# DSI_LCD.net
KiCad netlist of a schematic drawn in Altium Designer
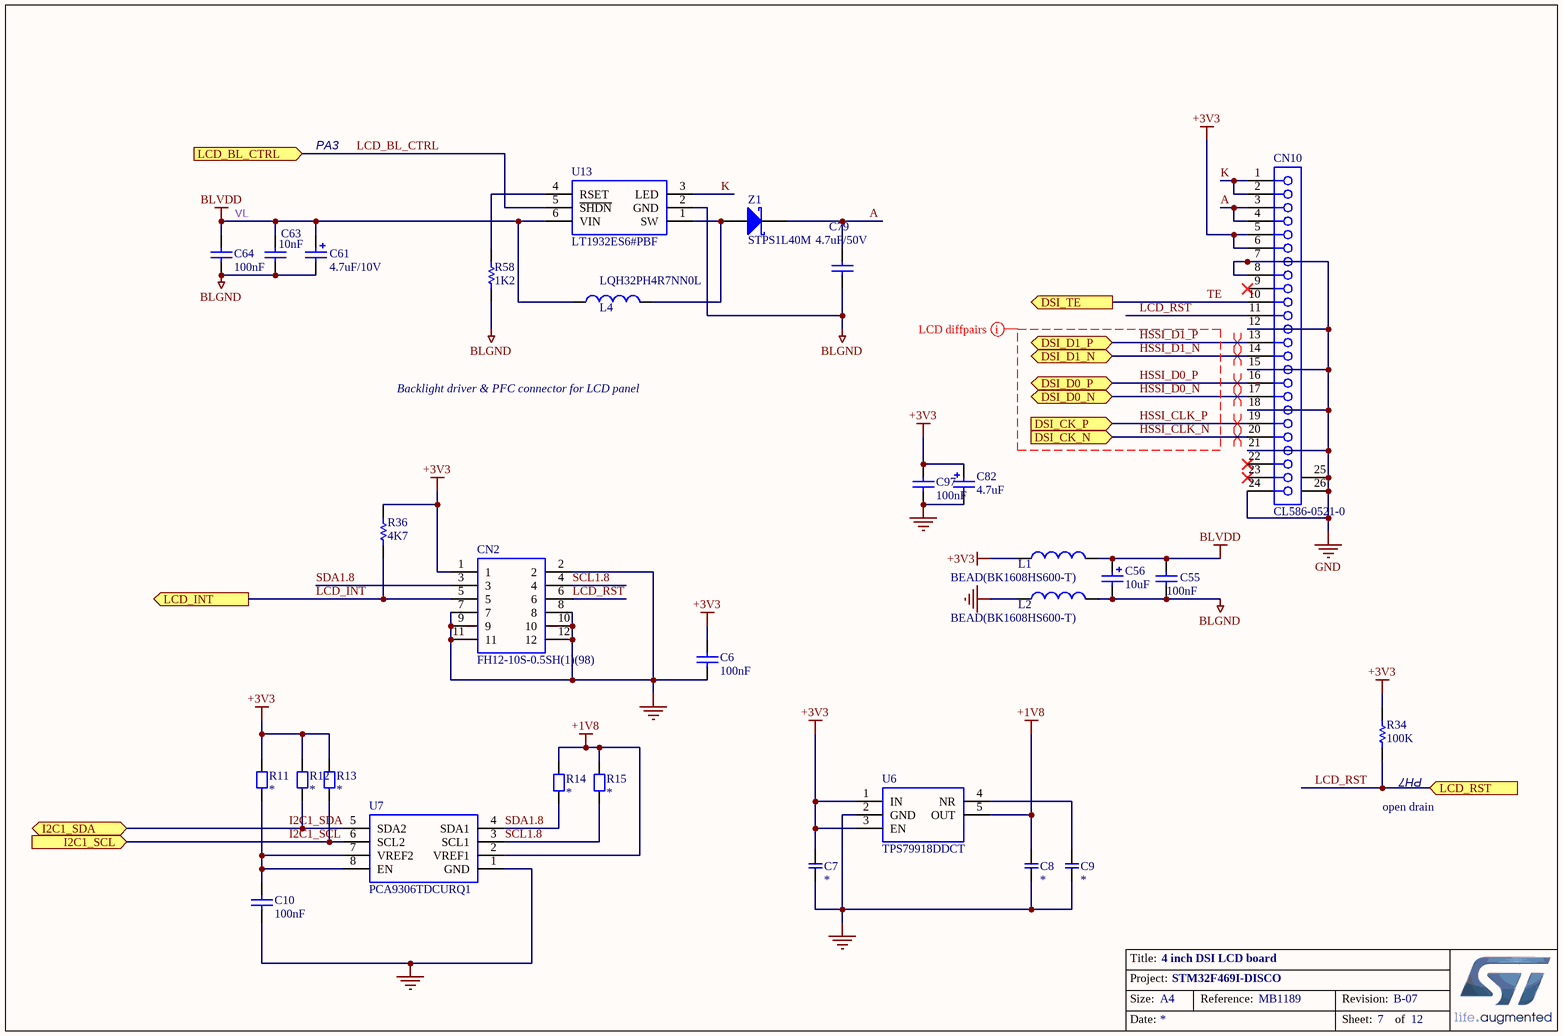
[diagram p0: DSI_LCD.SchDoc]

(export (version "E")
  (design (tool "Eeschema 10.0.6"))
  (components
    (comp (ref "C6")
      (value "100nF")
      (footprint "CAP - 0402")
      (description "Capacitor")
      (fields (field (name "PUBLISHER") "Altium Limited"))
      (libsource (lib "Miscellaneous Devices") (part "CAP"))
    )
    (comp (ref "C7")
      (value "100nF")
      (footprint "CAP - 0402")
      (fields (field (name "ALTIUM_VALUE") "*"))
      (libsource (lib "passives") (part "capacitor"))
    )
    (comp (ref "C8")
      (value "2.2uF")
      (footprint "CAP - 0402")
      (fields (field (name "ALTIUM_VALUE") "*"))
      (libsource (lib "passives") (part "capacitor"))
    )
    (comp (ref "C9")
      (value "10uF")
      (footprint "CAP - 0402")
      (fields (field (name "ALTIUM_VALUE") "*"))
      (libsource (lib "passives") (part "capacitor"))
    )
    (comp (ref "C10")
      (value "100nF")
      (footprint "CAP - 0402")
      (description "Capacitor")
      (fields (field (name "PUBLISHER") "Altium Limited"))
      (libsource (lib "Miscellaneous Devices") (part "CAP"))
    )
    (comp (ref "C55")
      (value "100nF")
      (footprint "CAP - 0402")
      (description "Capacitor")
      (fields (field (name "PUBLISHER") "Altium Limited"))
      (libsource (lib "Miscellaneous Devices") (part "Cap"))
    )
    (comp (ref "C56")
      (value "10uF")
      (footprint "KEMET Electronics Footprints:A")
      (description "Polarized Capacitor (Radial)")
      (fields (field (name "PUBLISHER") "Altium Limited"))
      (libsource (lib "Miscellaneous Devices") (part "Cap Pol1"))
    )
    (comp (ref "C61")
      (value "4.7uF/10V")
      (footprint "CAP - 1206")
      (description "Polarized Capacitor (Radial)")
      (fields (field (name "PUBLISHER") "Altium Limited"))
      (libsource (lib "Miscellaneous Devices") (part "Cap Pol1"))
    )
    (comp (ref "C63")
      (value "10nF")
      (footprint "CAP - 0402")
      (description "Capacitor")
      (fields (field (name "PUBLISHER") "Altium Limited"))
      (libsource (lib "Miscellaneous Devices") (part "CAP"))
    )
    (comp (ref "C64")
      (value "100nF")
      (footprint "CAP - 0402")
      (description "Capacitor")
      (fields (field (name "PUBLISHER") "Altium Limited"))
      (libsource (lib "Miscellaneous Devices") (part "CAP"))
    )
    (comp (ref "C79")
      (value "4.7uF/50V")
      (footprint "CAP - 1206")
      (description "Capacitor")
      (fields (field (name "PUBLISHER") "Altium Limited"))
      (libsource (lib "Miscellaneous Devices") (part "CAP"))
    )
    (comp (ref "C82")
      (value "4.7uF")
      (footprint "KEMET Electronics Footprints:A")
      (description "Polarized Capacitor (Radial)")
      (fields (field (name "PUBLISHER") "Altium Limited"))
      (libsource (lib "Miscellaneous Devices") (part "Cap Pol1"))
    )
    (comp (ref "C97")
      (value "100nF")
      (footprint "CAP - 0402")
      (description "Capacitor")
      (fields (field (name "PUBLISHER") "Altium Limited"))
      (libsource (lib "Miscellaneous Devices") (part "CAP"))
    )
    (comp (ref "CN2")
      (value "FH12-10S-0.5SH(1)(98)")
      (footprint "FH1210S05SH198")
      (description "FFC & FPC Connectors 10P SMT HORIZONTAL .5MM PITCH")
      (libsource (lib "FH12-10S-0.5SH(1)(98)") (part "FH12-10S-0.5SH(1)(98)"))
    )
    (comp (ref "CN10")
      (value "CL586-0521-0")
      (footprint "FH12-24S-0.5SH")
      (description "FH12 Series, \"Flip-Lock\" SMT/ZIF FFC/FPC Connector - 0.5mm Spaced Bottom Contact")
      (fields (field (name "PUBLISHER") "Altium Limited"))
      (libsource (lib "HRS FPC-FFC FH12 Series") (part "CL586-0521-0"))
    )
    (comp (ref "L1")
      (value "BEAD(BK1608HS600-T)")
      (footprint "1608[0603]")
      (description "Inductor")
      (fields (field (name "PUBLISHER") "Altium Limited"))
      (libsource (lib "Miscellaneous Devices") (part "Inductor"))
    )
    (comp (ref "L2")
      (value "BEAD(BK1608HS600-T)")
      (footprint "1608[0603]")
      (description "Inductor")
      (fields (field (name "PUBLISHER") "Altium Limited"))
      (libsource (lib "Miscellaneous Devices") (part "Inductor"))
    )
    (comp (ref "L4")
      (value "LQH32PH4R7NN0L")
      (footprint "C1210_L")
      (description "Inductor")
      (fields (field (name "PUBLISHER") "Altium Limited"))
      (libsource (lib "Miscellaneous Devices") (part "Inductor"))
    )
    (comp (ref "R11")
      (value "200K")
      (footprint "RES - 0402")
      (fields (field (name "ALTIUM_VALUE") "*"))
      (libsource (lib "passives") (part "resistor"))
    )
    (comp (ref "R12")
      (value "2K7")
      (footprint "RES - 0402")
      (fields (field (name "ALTIUM_VALUE") "*"))
      (libsource (lib "passives") (part "resistor"))
    )
    (comp (ref "R13")
      (value "2K7")
      (footprint "RES - 0402")
      (fields (field (name "ALTIUM_VALUE") "*"))
      (libsource (lib "passives") (part "resistor"))
    )
    (comp (ref "R14")
      (value "1K5")
      (footprint "RES - 0402")
      (fields (field (name "ALTIUM_VALUE") "*"))
      (libsource (lib "passives") (part "resistor"))
    )
    (comp (ref "R15")
      (value "1K5")
      (footprint "RES - 0402")
      (fields (field (name "ALTIUM_VALUE") "*"))
      (libsource (lib "passives") (part "resistor"))
    )
    (comp (ref "R34")
      (value "100K")
      (footprint "RES - 0402")
      (description "Resistor")
      (fields (field (name "PUBLISHER") "Altium Limited"))
      (libsource (lib "Miscellaneous Devices") (part "Res1"))
    )
    (comp (ref "R36")
      (value "4K7")
      (footprint "RES - 0402")
      (description "Resistor")
      (fields (field (name "PUBLISHER") "Altium Limited"))
      (libsource (lib "*") (part "Res1"))
    )
    (comp (ref "R58")
      (value "1K2")
      (footprint "RES - 0402")
      (description "Resistor")
      (fields (field (name "PUBLISHER") "Altium Limited"))
      (libsource (lib "Miscellaneous Devices") (part "Res1"))
    )
    (comp (ref "U6")
      (value "TPS79918DDCT")
      (footprint "SOT95P280X110-5N")
      (description "TPS79918DDCT, Low Dropout Voltage Regulator, 0.2A, 1.8V 1%, 2.7 to 6.5Vin, 5-Pin SOT")
      (fields
        (field (name "RS PART NUMBER") "1455973")
        (field (name "MOUSER PART NUMBER") "595-TPS79918DDCT")
      )
      (libsource (lib "TPS79918DDCT") (part "TPS79918DDCT"))
    )
    (comp (ref "U7")
      (value "PCA9306TDCURQ1")
      (footprint "SOP50P310X90-8N")
      (description "Automotive Dual Bidirectional I2C Bus and SMBus Voltage-Level Translator")
      (fields (field (name "MOUSER PART NUMBER") "595-PCA9306TDCURQ1"))
      (libsource (lib "PCA9306TDCURQ1") (part "PCA9306TDCURQ1"))
    )
    (comp (ref "U13")
      (value "LT1932ES6#PBF")
      (footprint "SOT95P280X145-6N")
      (description "LINEAR TECHNOLOGY - LT1932ES6#PBF - IC, DC/DC CONVERT/LED DR, 6SOT2")
      (fields (field (name "MOUSER PART NUMBER") "584-LT1932ES6#PBF"))
      (libsource (lib "LT1932ES6#PBF") (part "LT1932ES6#PBF"))
    )
    (comp (ref "Z1")
      (value "STPS1L40M")
      (footprint "DO-216AA")
      (description "Schottky Diode")
      (fields (field (name "PUBLISHER") "Altium Limited"))
      (libsource (lib "Miscellaneous Devices") (part "D Schottky"))
    )
  )
  (nets
    (net (code "1") (name "+1V8") (class "Default")
      (node (ref "C8") (pin "2") (pinfunction "2_2") (pintype "passive"))
      (node (ref "R14") (pin "2") (pinfunction "2_2") (pintype "passive"))
      (node (ref "R15") (pin "2") (pinfunction "2_2") (pintype "passive"))
      (node (ref "U6") (pin "5") (pinfunction "OUT_5") (pintype "passive"))
      (node (ref "U7") (pin "2") (pinfunction "VREF1_2") (pintype "power_in"))
    )
    (net (code "2") (name "+3V3") (class "Default")
      (node (ref "C6") (pin "2") (pinfunction "2_2") (pintype "passive"))
      (node (ref "C7") (pin "2") (pinfunction "2_2") (pintype "passive"))
      (node (ref "C82") (pin "1") (pinfunction "1_1") (pintype "passive"))
      (node (ref "C97") (pin "2") (pinfunction "2_2") (pintype "passive"))
      (node (ref "CN10") (pin "5") (pinfunction "5_5") (pintype "passive"))
      (node (ref "CN10") (pin "6") (pinfunction "6_6") (pintype "passive"))
      (node (ref "CN2") (pin "1") (pinfunction "1_1") (pintype "passive"))
      (node (ref "L1") (pin "1") (pinfunction "1_1") (pintype "passive"))
      (node (ref "R11") (pin "2") (pinfunction "2_2") (pintype "passive"))
      (node (ref "R12") (pin "2") (pinfunction "2_2") (pintype "passive"))
      (node (ref "R13") (pin "2") (pinfunction "2_2") (pintype "passive"))
      (node (ref "R34") (pin "1") (pinfunction "1_1") (pintype "passive"))
      (node (ref "R36") (pin "1") (pinfunction "1_1") (pintype "passive"))
      (node (ref "U6") (pin "1") (pinfunction "IN_1") (pintype "passive"))
      (node (ref "U6") (pin "3") (pinfunction "EN_3") (pintype "passive"))
    )
    (net (code "3") (name "/A") (class "Default")
      (node (ref "C79") (pin "1") (pinfunction "1_1") (pintype "passive"))
      (node (ref "CN10") (pin "3") (pinfunction "3_3") (pintype "passive"))
      (node (ref "CN10") (pin "4") (pinfunction "4_4") (pintype "passive"))
      (node (ref "Z1") (pin "2") (pinfunction "K_2") (pintype "passive"))
    )
    (net (code "4") (name "/HSSI_CLK_N") (class "Default")
      (node (ref "CN10") (pin "20") (pinfunction "20_20") (pintype "passive"))
    )
    (net (code "5") (name "/HSSI_CLK_P") (class "Default")
      (node (ref "CN10") (pin "19") (pinfunction "19_19") (pintype "passive"))
    )
    (net (code "6") (name "/HSSI_D0_N") (class "Default")
      (node (ref "CN10") (pin "17") (pinfunction "17_17") (pintype "passive"))
    )
    (net (code "7") (name "/HSSI_D0_P") (class "Default")
      (node (ref "CN10") (pin "16") (pinfunction "16_16") (pintype "passive"))
    )
    (net (code "8") (name "/HSSI_D1_N") (class "Default")
      (node (ref "CN10") (pin "14") (pinfunction "14_14") (pintype "passive"))
    )
    (net (code "9") (name "/HSSI_D1_P") (class "Default")
      (node (ref "CN10") (pin "13") (pinfunction "13_13") (pintype "passive"))
    )
    (net (code "10") (name "/I2C1_SCL") (class "Default")
      (node (ref "R13") (pin "1") (pinfunction "1_1") (pintype "passive"))
      (node (ref "U7") (pin "6") (pinfunction "SCL2_6") (pintype "passive"))
    )
    (net (code "11") (name "/I2C1_SDA") (class "Default")
      (node (ref "R12") (pin "1") (pinfunction "1_1") (pintype "passive"))
      (node (ref "U7") (pin "5") (pinfunction "SDA2_5") (pintype "passive"))
    )
    (net (code "12") (name "/K") (class "Default")
      (node (ref "CN10") (pin "1") (pinfunction "1_1") (pintype "passive"))
      (node (ref "CN10") (pin "2") (pinfunction "2_2") (pintype "passive"))
      (node (ref "U13") (pin "3") (pinfunction "LED_3") (pintype "passive"))
    )
    (net (code "13") (name "/LCD_BL_CTRL") (class "Default")
      (node (ref "U13") (pin "5") (pinfunction "SHDN_5") (pintype "passive"))
    )
    (net (code "14") (name "/LCD_INT") (class "Default")
      (node (ref "CN2") (pin "5") (pinfunction "5_5") (pintype "passive"))
      (node (ref "R36") (pin "2") (pinfunction "2_2") (pintype "passive"))
    )
    (net (code "15") (name "/LCD_RST") (class "Default")
      (node (ref "CN10") (pin "11") (pinfunction "11_11") (pintype "passive"))
      (node (ref "CN2") (pin "6") (pinfunction "6_6") (pintype "passive"))
      (node (ref "R34") (pin "2") (pinfunction "2_2") (pintype "passive"))
    )
    (net (code "16") (name "/SCL1.8") (class "Default")
      (node (ref "CN2") (pin "4") (pinfunction "4_4") (pintype "passive"))
      (node (ref "R15") (pin "1") (pinfunction "1_1") (pintype "passive"))
      (node (ref "U7") (pin "3") (pinfunction "SCL1_3") (pintype "passive"))
    )
    (net (code "17") (name "/SDA1.8") (class "Default")
      (node (ref "CN2") (pin "3") (pinfunction "3_3") (pintype "passive"))
      (node (ref "R14") (pin "1") (pinfunction "1_1") (pintype "passive"))
      (node (ref "U7") (pin "4") (pinfunction "SDA1_4") (pintype "passive"))
    )
    (net (code "18") (name "/TE") (class "Default")
      (node (ref "CN10") (pin "10") (pinfunction "10_10") (pintype "passive"))
    )
    (net (code "19") (name "BLGND") (class "Default")
      (node (ref "C55") (pin "2") (pinfunction "2_2") (pintype "passive"))
      (node (ref "C56") (pin "2") (pinfunction "2_2") (pintype "passive"))
      (node (ref "C61") (pin "2") (pinfunction "2_2") (pintype "passive"))
      (node (ref "C63") (pin "1") (pinfunction "1_1") (pintype "passive"))
      (node (ref "C64") (pin "1") (pinfunction "1_1") (pintype "passive"))
      (node (ref "C79") (pin "2") (pinfunction "2_2") (pintype "passive"))
      (node (ref "L2") (pin "2") (pinfunction "2_2") (pintype "passive"))
      (node (ref "R58") (pin "1") (pinfunction "1_1") (pintype "passive"))
      (node (ref "U13") (pin "2") (pinfunction "GND_2") (pintype "passive"))
    )
    (net (code "20") (name "BLVDD") (class "Default")
      (node (ref "C55") (pin "1") (pinfunction "1_1") (pintype "passive"))
      (node (ref "C56") (pin "1") (pinfunction "1_1") (pintype "passive"))
      (node (ref "C61") (pin "1") (pinfunction "1_1") (pintype "passive"))
      (node (ref "C63") (pin "2") (pinfunction "2_2") (pintype "passive"))
      (node (ref "C64") (pin "2") (pinfunction "2_2") (pintype "passive"))
      (node (ref "L1") (pin "2") (pinfunction "2_2") (pintype "passive"))
      (node (ref "L4") (pin "1") (pinfunction "1_1") (pintype "passive"))
      (node (ref "U13") (pin "6") (pinfunction "VIN_6") (pintype "passive"))
    )
    (net (code "21") (name "GND") (class "Default")
      (node (ref "C10") (pin "1") (pinfunction "1_1") (pintype "passive"))
      (node (ref "C6") (pin "1") (pinfunction "1_1") (pintype "passive"))
      (node (ref "C7") (pin "1") (pinfunction "1_1") (pintype "passive"))
      (node (ref "C8") (pin "1") (pinfunction "1_1") (pintype "passive"))
      (node (ref "C82") (pin "2") (pinfunction "2_2") (pintype "passive"))
      (node (ref "C9") (pin "1") (pinfunction "1_1") (pintype "passive"))
      (node (ref "C97") (pin "1") (pinfunction "1_1") (pintype "passive"))
      (node (ref "CN10") (pin "12") (pinfunction "12_12") (pintype "passive"))
      (node (ref "CN10") (pin "15") (pinfunction "15_15") (pintype "passive"))
      (node (ref "CN10") (pin "18") (pinfunction "18_18") (pintype "passive"))
      (node (ref "CN10") (pin "21") (pinfunction "21_21") (pintype "passive"))
      (node (ref "CN10") (pin "24") (pinfunction "24_24") (pintype "passive"))
      (node (ref "CN10") (pin "25") (pinfunction "MH1_25") (pintype "passive"))
      (node (ref "CN10") (pin "26") (pinfunction "MH2_26") (pintype "passive"))
      (node (ref "CN10") (pin "7") (pinfunction "7_7") (pintype "passive"))
      (node (ref "CN10") (pin "8") (pinfunction "8_8") (pintype "passive"))
      (node (ref "CN2") (pin "10") (pinfunction "10_10") (pintype "passive"))
      (node (ref "CN2") (pin "11") (pinfunction "11_11") (pintype "passive"))
      (node (ref "CN2") (pin "12") (pinfunction "12_12") (pintype "passive"))
      (node (ref "CN2") (pin "2") (pinfunction "2_2") (pintype "passive"))
      (node (ref "CN2") (pin "7") (pinfunction "7_7") (pintype "passive"))
      (node (ref "CN2") (pin "8") (pinfunction "8_8") (pintype "passive"))
      (node (ref "CN2") (pin "9") (pinfunction "9_9") (pintype "passive"))
      (node (ref "L2") (pin "1") (pinfunction "1_1") (pintype "passive"))
      (node (ref "U6") (pin "2") (pinfunction "GND_2") (pintype "passive"))
      (node (ref "U7") (pin "1") (pinfunction "GND_1") (pintype "passive"))
    )
    (net (code "22") (name "Net-(U6-NR)") (class "Default")
      (node (ref "C9") (pin "2") (pinfunction "2_2") (pintype "passive"))
      (node (ref "U6") (pin "4") (pinfunction "NR_4") (pintype "passive"))
    )
    (net (code "23") (name "Net-(U7-EN)") (class "Default")
      (node (ref "C10") (pin "2") (pinfunction "2_2") (pintype "passive"))
      (node (ref "R11") (pin "1") (pinfunction "1_1") (pintype "passive"))
      (node (ref "U7") (pin "7") (pinfunction "VREF2_7") (pintype "power_in"))
      (node (ref "U7") (pin "8") (pinfunction "EN_8") (pintype "passive"))
    )
    (net (code "24") (name "Net-(U13-RSET)") (class "Default")
      (node (ref "R58") (pin "2") (pinfunction "2_2") (pintype "passive"))
      (node (ref "U13") (pin "4") (pinfunction "RSET_4") (pintype "passive"))
    )
    (net (code "25") (name "Net-(U13-SW)") (class "Default")
      (node (ref "L4") (pin "2") (pinfunction "2_2") (pintype "passive"))
      (node (ref "U13") (pin "1") (pinfunction "SW_1") (pintype "passive"))
      (node (ref "Z1") (pin "1") (pinfunction "A_1") (pintype "passive"))
    )
    (net (code "26") (name "unconnected-(CN10-Pad9)") (class "Default")
      (node (ref "CN10") (pin "9") (pinfunction "9_9") (pintype "passive+no_connect"))
    )
    (net (code "27") (name "unconnected-(CN10-Pad22)") (class "Default")
      (node (ref "CN10") (pin "22") (pinfunction "22_22") (pintype "passive+no_connect"))
    )
    (net (code "28") (name "unconnected-(CN10-Pad23)") (class "Default")
      (node (ref "CN10") (pin "23") (pinfunction "23_23") (pintype "passive+no_connect"))
    )
  )
)
